# SchemaA-puissance.net
KiCad netlist of a schematic drawn in Altium Designer
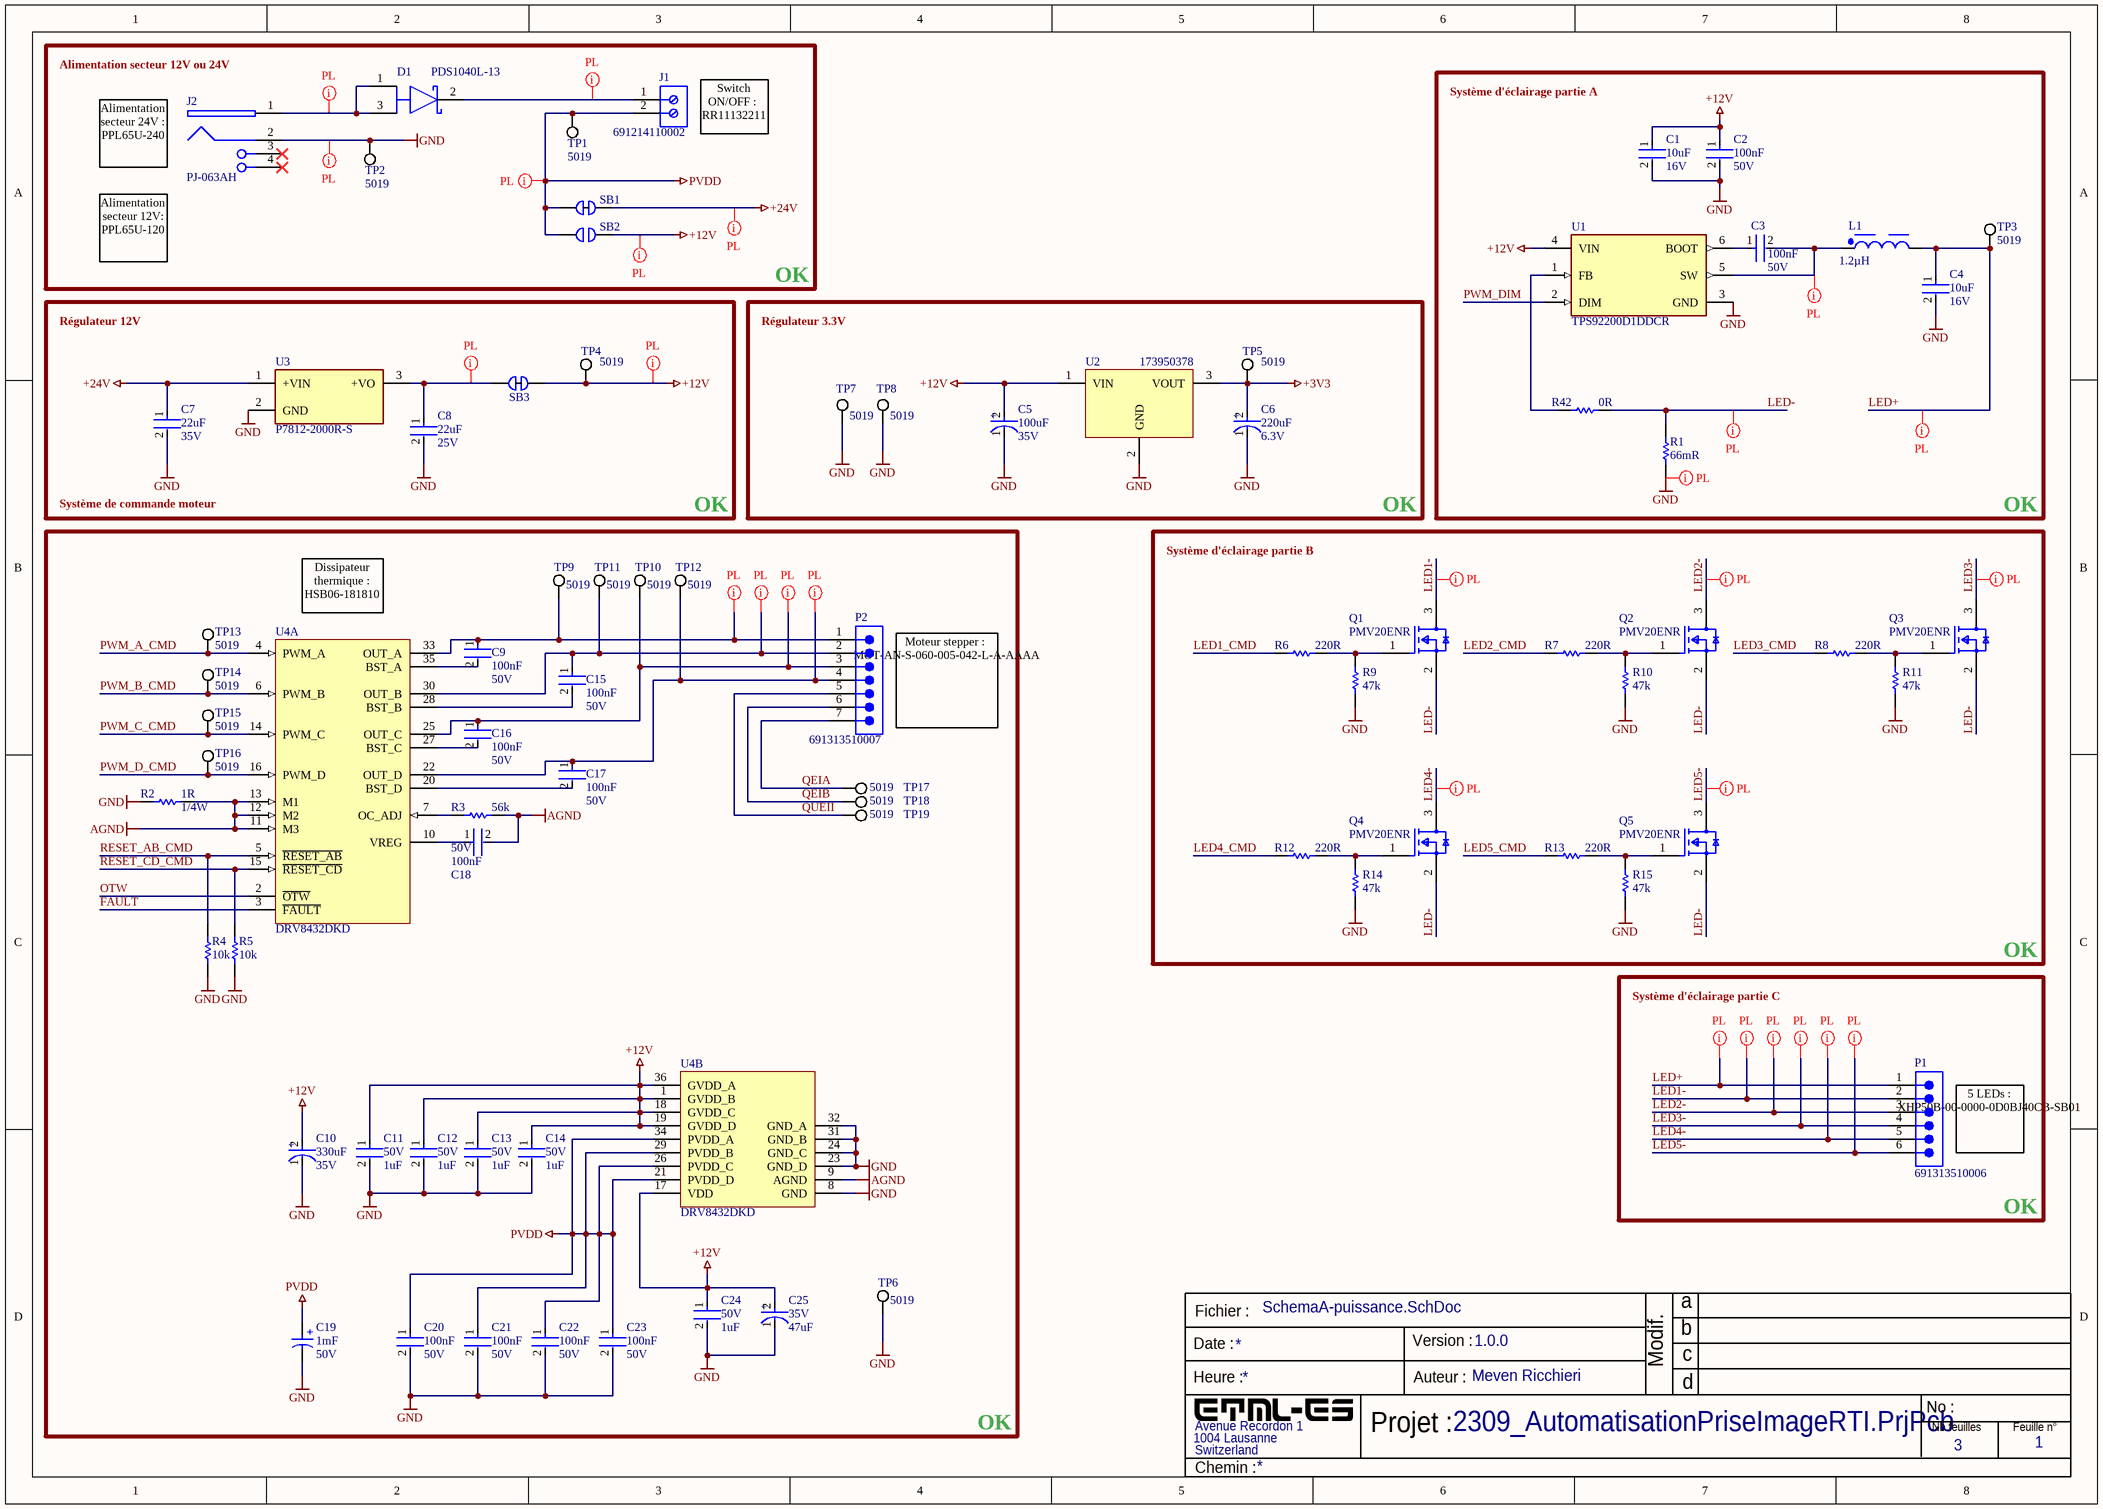
[diagram p0: SchemaA-puissance.SchDoc]

(export (version "E")
  (design (tool "Eeschema 10.0.6"))
  (components
    (comp (ref "C1")
      (value "CL21A106KOQNNNE")
      (footprint "FP-CL21-IPC_B")
      (description "CL21 Series 0805 10uF 16V ±10% Tolerance X5R Multilayer Ceramic Chip Capacitor")
      (fields
        (field (name "VOLTAGE") "16V")
        (field (name "CAPACITANCE") "10uF")
        (field (name "VOLTAGE RATING") "16V")
        (field (name "TOLERANCE") "10%")
      )
      (libsource (lib "Altium Content Vault") (part "b4654b650e69147ec39a6b967a45e02"))
    )
    (comp (ref "C2")
      (value "CL21B104KBCNNNC")
      (footprint "FP-CL21-IPC_C")
      (description "CL21 Series 0805 100nF 50V ±10% Tolerance X7R Multilayer Ceramic Chip Capacitor")
      (fields
        (field (name "TOLERANCE") "10%")
        (field (name "CAPACITANCE") "100nF")
        (field (name "VOLTAGE RATING") "50V")
        (field (name "VOLTAGE") "50V")
      )
      (libsource (lib "Altium Content Vault") (part "b4654b650e69147ec39a6b967a45e02"))
    )
    (comp (ref "C3")
      (value "CL21B104KBCNNNC")
      (footprint "FP-CL21-IPC_C")
      (description "CL21 Series 0805 100nF 50V ±10% Tolerance X7R Multilayer Ceramic Chip Capacitor")
      (fields
        (field (name "TOLERANCE") "10%")
        (field (name "CAPACITANCE") "100nF")
        (field (name "VOLTAGE RATING") "50V")
        (field (name "VOLTAGE") "50V")
      )
      (libsource (lib "Altium Content Vault") (part "b4654b650e69147ec39a6b967a45e02"))
    )
    (comp (ref "C4")
      (value "CL21A106KOQNNNE")
      (footprint "FP-CL21-IPC_B")
      (description "CL21 Series 0805 10uF 16V ±10% Tolerance X5R Multilayer Ceramic Chip Capacitor")
      (fields
        (field (name "VOLTAGE") "16V")
        (field (name "CAPACITANCE") "10uF")
        (field (name "VOLTAGE RATING") "16V")
        (field (name "TOLERANCE") "10%")
      )
      (libsource (lib "Altium Content Vault") (part "b4654b650e69147ec39a6b967a45e02"))
    )
    (comp (ref "C5")
      (value "EEE-1VA101XP")
      (footprint "FP-SD8-MFG")
      (description "CAP ALUM 100UF 20% 35V SMD")
      (fields
        (field (name "CAPACITANCE") "100uF")
        (field (name "TOLERANCE") "20%")
        (field (name "VOLTAGE") "35V")
      )
      (libsource (lib "Altium Content Vault") (part "a00bbbee19879c290e62620ae7e47b1"))
    )
    (comp (ref "C6")
      (value "EEE-FK0J221P")
      (footprint "FP-FKD-MFG")
      (description "CAP ALUM 220UF 20% 6.3V SMD")
      (fields
        (field (name "VOLTAGE RATING") "6.3V")
        (field (name "VOLTAGE") "6.3V")
        (field (name "CAPACITANCE") "220uF")
        (field (name "TOLERANCE") "20%")
      )
      (libsource (lib "Altium Content Vault") (part "a00bbbee19879c290e62620ae7e47b1"))
    )
    (comp (ref "C7")
      (value "GMK325BJ226MM-P")
      (footprint "FP-1210-L_3_2_0_3-W_2_5_0-MFG")
      (description "None")
      (fields
        (field (name "CAPACITANCE") "22uF")
        (field (name "VOLTAGE RATING") "35V")
        (field (name "TOLERANCE") "20%")
      )
      (libsource (lib "Altium Content Vault") (part "02cd4be3c70576c341d710602a673aa"))
    )
    (comp (ref "C8")
      (value "22uF")
      (footprint "FP-CL21-IPC_C")
      (description "CL21 Series 0805 22uF 25V ±20% Tolerance X5R Multilayer Ceramic Chip Capacitor")
      (fields (field (name "VOLTAGE") "25V") (field (name "Comment") "CL21A226MAYNNNE"))
      (libsource (lib "Altium Content Vault") (part "b4654b650e69147ec39a6b967a45e02"))
    )
    (comp (ref "C9")
      (value "CL21B104KBCNNNC")
      (footprint "FP-CL21-IPC_C")
      (description "CL21 Series 0805 100nF 50V ±10% Tolerance X7R Multilayer Ceramic Chip Capacitor")
      (fields
        (field (name "TOLERANCE") "10%")
        (field (name "CAPACITANCE") "100nF")
        (field (name "VOLTAGE RATING") "50V")
        (field (name "VOLTAGE") "50V")
      )
      (libsource (lib "Altium Content Vault") (part "b4654b650e69147ec39a6b967a45e02"))
    )
    (comp (ref "C10")
      (value "EEE-1VA331P")
      (footprint "FP-SG-MFG")
      (description "CAP ALUM 330UF 20% 35V SMD")
      (fields
        (field (name "VOLTAGE") "35V")
        (field (name "TOLERANCE") "20%")
        (field (name "CAPACITANCE") "330uF")
      )
      (libsource (lib "Altium Content Vault") (part "a00bbbee19879c290e62620ae7e47b1"))
    )
    (comp (ref "C11")
      (value "CL21B105KBFNNNG")
      (footprint "FP-CL21-IPC_C")
      (description "CL21 Series 0805 1uF 50V ±10% Tolerance X7R Multilayer Ceramic Chip Capacitor")
      (fields
        (field (name "CAPACITANCE") "1uF")
        (field (name "VOLTAGE") "50V")
        (field (name "TOLERANCE") "10%")
      )
      (libsource (lib "Altium Content Vault") (part "b4654b650e69147ec39a6b967a45e02"))
    )
    (comp (ref "C12")
      (value "CL21B105KBFNNNG")
      (footprint "FP-CL21-IPC_C")
      (description "CL21 Series 0805 1uF 50V ±10% Tolerance X7R Multilayer Ceramic Chip Capacitor")
      (fields
        (field (name "CAPACITANCE") "1uF")
        (field (name "VOLTAGE") "50V")
        (field (name "TOLERANCE") "10%")
      )
      (libsource (lib "Altium Content Vault") (part "b4654b650e69147ec39a6b967a45e02"))
    )
    (comp (ref "C13")
      (value "CL21B105KBFNNNG")
      (footprint "FP-CL21-IPC_C")
      (description "CL21 Series 0805 1uF 50V ±10% Tolerance X7R Multilayer Ceramic Chip Capacitor")
      (fields
        (field (name "CAPACITANCE") "1uF")
        (field (name "VOLTAGE") "50V")
        (field (name "TOLERANCE") "10%")
      )
      (libsource (lib "Altium Content Vault") (part "b4654b650e69147ec39a6b967a45e02"))
    )
    (comp (ref "C14")
      (value "CL21B105KBFNNNG")
      (footprint "FP-CL21-IPC_C")
      (description "CL21 Series 0805 1uF 50V ±10% Tolerance X7R Multilayer Ceramic Chip Capacitor")
      (fields
        (field (name "CAPACITANCE") "1uF")
        (field (name "VOLTAGE") "50V")
        (field (name "TOLERANCE") "10%")
      )
      (libsource (lib "Altium Content Vault") (part "b4654b650e69147ec39a6b967a45e02"))
    )
    (comp (ref "C15")
      (value "CL21B104KBCNNNC")
      (footprint "FP-CL21-IPC_C")
      (description "CL21 Series 0805 100nF 50V ±10% Tolerance X7R Multilayer Ceramic Chip Capacitor")
      (fields
        (field (name "TOLERANCE") "10%")
        (field (name "CAPACITANCE") "100nF")
        (field (name "VOLTAGE RATING") "50V")
        (field (name "VOLTAGE") "50V")
      )
      (libsource (lib "Altium Content Vault") (part "b4654b650e69147ec39a6b967a45e02"))
    )
    (comp (ref "C16")
      (value "CL21B104KBCNNNC")
      (footprint "FP-CL21-IPC_C")
      (description "CL21 Series 0805 100nF 50V ±10% Tolerance X7R Multilayer Ceramic Chip Capacitor")
      (fields
        (field (name "TOLERANCE") "10%")
        (field (name "CAPACITANCE") "100nF")
        (field (name "VOLTAGE RATING") "50V")
        (field (name "VOLTAGE") "50V")
      )
      (libsource (lib "Altium Content Vault") (part "b4654b650e69147ec39a6b967a45e02"))
    )
    (comp (ref "C17")
      (value "CL21B104KBCNNNC")
      (footprint "FP-CL21-IPC_C")
      (description "CL21 Series 0805 100nF 50V ±10% Tolerance X7R Multilayer Ceramic Chip Capacitor")
      (fields
        (field (name "TOLERANCE") "10%")
        (field (name "CAPACITANCE") "100nF")
        (field (name "VOLTAGE RATING") "50V")
        (field (name "VOLTAGE") "50V")
      )
      (libsource (lib "Altium Content Vault") (part "b4654b650e69147ec39a6b967a45e02"))
    )
    (comp (ref "C18")
      (value "CL21B104KBCNNNC")
      (footprint "FP-CL21-IPC_C")
      (description "CL21 Series 0805 100nF 50V ±10% Tolerance X7R Multilayer Ceramic Chip Capacitor")
      (fields
        (field (name "TOLERANCE") "10%")
        (field (name "CAPACITANCE") "100nF")
        (field (name "VOLTAGE RATING") "50V")
        (field (name "VOLTAGE") "50V")
      )
      (libsource (lib "Altium Content Vault") (part "b4654b650e69147ec39a6b967a45e02"))
    )
    (comp (ref "C19")
      (value "865080663020")
      (footprint "WCAP-ASLI_D16H17")
      (description "865080663020 WCAP-ASLI Aluminum Electrolytic Capacitors")
      (fields
        (field (name "CAPACITANCE") "1mF")
        (field (name "VOLTAGE RATING") "50V")
        (field (name "TOLERANCE") "20%")
      )
      (libsource (lib "Altium Content Vault") (part "Capacitor_Polarized"))
    )
    (comp (ref "C20")
      (value "CL21B104KBCNNNC")
      (footprint "FP-CL21-IPC_C")
      (description "CL21 Series 0805 100nF 50V ±10% Tolerance X7R Multilayer Ceramic Chip Capacitor")
      (fields
        (field (name "TOLERANCE") "10%")
        (field (name "CAPACITANCE") "100nF")
        (field (name "VOLTAGE RATING") "50V")
        (field (name "VOLTAGE") "50V")
      )
      (libsource (lib "Altium Content Vault") (part "b4654b650e69147ec39a6b967a45e02"))
    )
    (comp (ref "C21")
      (value "CL21B104KBCNNNC")
      (footprint "FP-CL21-IPC_C")
      (description "CL21 Series 0805 100nF 50V ±10% Tolerance X7R Multilayer Ceramic Chip Capacitor")
      (fields
        (field (name "TOLERANCE") "10%")
        (field (name "CAPACITANCE") "100nF")
        (field (name "VOLTAGE RATING") "50V")
        (field (name "VOLTAGE") "50V")
      )
      (libsource (lib "Altium Content Vault") (part "b4654b650e69147ec39a6b967a45e02"))
    )
    (comp (ref "C22")
      (value "CL21B104KBCNNNC")
      (footprint "FP-CL21-IPC_C")
      (description "CL21 Series 0805 100nF 50V ±10% Tolerance X7R Multilayer Ceramic Chip Capacitor")
      (fields
        (field (name "TOLERANCE") "10%")
        (field (name "CAPACITANCE") "100nF")
        (field (name "VOLTAGE RATING") "50V")
        (field (name "VOLTAGE") "50V")
      )
      (libsource (lib "Altium Content Vault") (part "b4654b650e69147ec39a6b967a45e02"))
    )
    (comp (ref "C23")
      (value "CL21B104KBCNNNC")
      (footprint "FP-CL21-IPC_C")
      (description "CL21 Series 0805 100nF 50V ±10% Tolerance X7R Multilayer Ceramic Chip Capacitor")
      (fields
        (field (name "TOLERANCE") "10%")
        (field (name "CAPACITANCE") "100nF")
        (field (name "VOLTAGE RATING") "50V")
        (field (name "VOLTAGE") "50V")
      )
      (libsource (lib "Altium Content Vault") (part "b4654b650e69147ec39a6b967a45e02"))
    )
    (comp (ref "C24")
      (value "CL21B105KBFNNNG")
      (footprint "FP-CL21-IPC_C")
      (description "CL21 Series 0805 1uF 50V ±10% Tolerance X7R Multilayer Ceramic Chip Capacitor")
      (fields
        (field (name "CAPACITANCE") "1uF")
        (field (name "VOLTAGE") "50V")
        (field (name "TOLERANCE") "10%")
      )
      (libsource (lib "Altium Content Vault") (part "b4654b650e69147ec39a6b967a45e02"))
    )
    (comp (ref "C25")
      (value "EEEFP1V470AP")
      (footprint "FP-FPD-MFG")
      (description "CAP ALUM 47UF 20% 35V SMD")
      (fields
        (field (name "VOLTAGE RATING (DC)") "35V")
        (field (name "TOLERANCE") "20%")
        (field (name "CAPACITANCE") "47uF")
        (field (name "VOLTAGE") "35V")
      )
      (libsource (lib "Altium Content Vault") (part "cf48714ba7e38822c1575c7ec0b6d1f"))
    )
    (comp (ref "D1")
      (value "PDS1040L-13")
      (footprint "FP-PowerDI5-MFG")
      (description "DIODE SCHOTTKY 40V 10A POWERDI5")
      (fields
        (field (name "OCTOPART") "https://octopart.com/pds1040l-13-diodes+inc.-332540")
        (field (name "MANUFACTURER") "Diodes Inc.")
      )
      (libsource (lib "Altium Content Vault") (part "742f7ab95c42997246ebbe41a6c66ae"))
    )
    (comp (ref "J1")
      (value "691214110002")
      (footprint "691214110002")
      (fields (field (name "VOLTAGE") "300V"))
      (libsource (lib "Altium Content Vault") (part "TBL - 1R - 02P - Screw"))
    )
    (comp (ref "J2")
      (value "PJ-063AH")
      (footprint "CUI-PJ-063AH_V")
      (fields (field (name "MANUFACTURER") "CUIInc."))
      (libsource (lib "Altium Content Vault") (part "JACK-2CD2_A"))
    )
    (comp (ref "L1")
      (value "7440430012")
      (footprint "WE-TPC_4828")
      (fields (field (name "TOLERANCE") "30%") (field (name "INDUCTANCE") "1.2µH"))
      (libsource (lib "Altium Content Vault") (part "Inductor - 2"))
    )
    (comp (ref "P1")
      (value "691313510006")
      (footprint "691313510006")
      (fields (field (name "VOLTAGE") "300V"))
      (libsource (lib "Altium Content Vault") (part "TBL - 1R - 06P - Male"))
    )
    (comp (ref "P2")
      (value "691313510007")
      (footprint "691313510007")
      (libsource (lib "Altium Content Vault") (part "TBL - 1R - 07P - Male"))
    )
    (comp (ref "Q1")
      (value "PMV20ENR")
      (footprint "FP-SOT23-MFG")
      (description "MOSFET N-CH 30V SOT23")
      (libsource (lib "Altium Content Vault") (part "0a9ea7c96deaaede766a5b531c28de0"))
    )
    (comp (ref "Q2")
      (value "PMV20ENR")
      (footprint "FP-SOT23-MFG")
      (description "MOSFET N-CH 30V SOT23")
      (libsource (lib "Altium Content Vault") (part "0a9ea7c96deaaede766a5b531c28de0"))
    )
    (comp (ref "Q3")
      (value "PMV20ENR")
      (footprint "FP-SOT23-MFG")
      (description "MOSFET N-CH 30V SOT23")
      (libsource (lib "Altium Content Vault") (part "0a9ea7c96deaaede766a5b531c28de0"))
    )
    (comp (ref "Q4")
      (value "PMV20ENR")
      (footprint "FP-SOT23-MFG")
      (description "MOSFET N-CH 30V SOT23")
      (libsource (lib "Altium Content Vault") (part "0a9ea7c96deaaede766a5b531c28de0"))
    )
    (comp (ref "Q5")
      (value "PMV20ENR")
      (footprint "FP-SOT23-MFG")
      (description "MOSFET N-CH 30V SOT23")
      (libsource (lib "Altium Content Vault") (part "0a9ea7c96deaaede766a5b531c28de0"))
    )
    (comp (ref "R1")
      (value "66mR")
      (footprint "6-0805_M")
      (description "Resistor")
      (fields (field (name "Comment") "ERJ-L06UF66MV") (field (name "PUBLISHER") "Altium Limited"))
      (libsource (lib "Miscellaneous Devices") (part "Res1"))
    )
    (comp (ref "R2")
      (value "1R")
      (footprint "RESC2013X60X30NL20T20")
      (fields
        (field (name "MANUFACTURER") "KOA Speer")
        (field (name "PART NUMBER") "RK73B2ATTD1R0J")
        (field (name "POWER") "1/4W")
      )
      (libsource (lib "Altium Content Vault") (part "RES"))
    )
    (comp (ref "R3")
      (value "56k")
      (footprint "RESC2013X70X40NL20T20")
      (fields (field (name "PART NUMBER") "ERJ6ENF5602V") (field (name "MANUFACTURER") "Panasonic"))
      (libsource (lib "Altium Content Vault") (part "RES"))
    )
    (comp (ref "R4")
      (value "RC0805JR-0710KL")
      (footprint "RESC2013X60X35ML10T20")
      (description "Chip Resistor, 10 KOhm, +/- 5%, 0.125 W, -55 to 155 degC, 0805 (2012 Metric), RoHS, Tape and Reel")
      (fields (field (name "MANUFACTURER") "Yageo") (field (name "RESISTANCE") "10k"))
      (libsource (lib "Altium Content Vault") (part "RES-2"))
    )
    (comp (ref "R5")
      (value "RC0805JR-0710KL")
      (footprint "RESC2013X60X35ML10T20")
      (description "Chip Resistor, 10 KOhm, +/- 5%, 0.125 W, -55 to 155 degC, 0805 (2012 Metric), RoHS, Tape and Reel")
      (fields (field (name "MANUFACTURER") "Yageo") (field (name "RESISTANCE") "10k"))
      (libsource (lib "Altium Content Vault") (part "RES-2"))
    )
    (comp (ref "R6")
      (value "220R")
      (footprint "RESC2013X70X40NL20T20")
      (fields (field (name "PART NUMBER") "ERJ6ENF2200V") (field (name "MANUFACTURER") "Panasonic"))
      (libsource (lib "Altium Content Vault") (part "RES"))
    )
    (comp (ref "R7")
      (value "220R")
      (footprint "RESC2013X70X40NL20T20")
      (fields (field (name "PART NUMBER") "ERJ6ENF2200V") (field (name "MANUFACTURER") "Panasonic"))
      (libsource (lib "Altium Content Vault") (part "RES"))
    )
    (comp (ref "R8")
      (value "220R")
      (footprint "RESC2013X70X40NL20T20")
      (fields (field (name "PART NUMBER") "ERJ6ENF2200V") (field (name "MANUFACTURER") "Panasonic"))
      (libsource (lib "Altium Content Vault") (part "RES"))
    )
    (comp (ref "R9")
      (value "47k")
      (footprint "RESC2013X60X35NL10T20")
      (description "Chip Resistor, 47 KOhm, +/- 1%, 0.125 W, -55 to 155 degC, 0805 (2012 Metric), RoHS, Tape and Reel")
      (fields (field (name "MANUFACTURER") "Yageo") (field (name "Comment") "RC0805FR-0747KL"))
      (libsource (lib "Altium Content Vault") (part "RES-2"))
    )
    (comp (ref "R10")
      (value "47k")
      (footprint "RESC2013X60X35NL10T20")
      (description "Chip Resistor, 47 KOhm, +/- 1%, 0.125 W, -55 to 155 degC, 0805 (2012 Metric), RoHS, Tape and Reel")
      (fields (field (name "MANUFACTURER") "Yageo") (field (name "Comment") "RC0805FR-0747KL"))
      (libsource (lib "Altium Content Vault") (part "RES-2"))
    )
    (comp (ref "R11")
      (value "47k")
      (footprint "RESC2013X60X35NL10T20")
      (description "Chip Resistor, 47 KOhm, +/- 1%, 0.125 W, -55 to 155 degC, 0805 (2012 Metric), RoHS, Tape and Reel")
      (fields (field (name "MANUFACTURER") "Yageo") (field (name "Comment") "RC0805FR-0747KL"))
      (libsource (lib "Altium Content Vault") (part "RES-2"))
    )
    (comp (ref "R12")
      (value "220R")
      (footprint "RESC2013X70X40NL20T20")
      (fields (field (name "PART NUMBER") "ERJ6ENF2200V") (field (name "MANUFACTURER") "Panasonic"))
      (libsource (lib "Altium Content Vault") (part "RES"))
    )
    (comp (ref "R13")
      (value "220R")
      (footprint "RESC2013X70X40NL20T20")
      (fields (field (name "PART NUMBER") "ERJ6ENF2200V") (field (name "MANUFACTURER") "Panasonic"))
      (libsource (lib "Altium Content Vault") (part "RES"))
    )
    (comp (ref "R14")
      (value "47k")
      (footprint "RESC2013X60X35NL10T20")
      (description "Chip Resistor, 47 KOhm, +/- 1%, 0.125 W, -55 to 155 degC, 0805 (2012 Metric), RoHS, Tape and Reel")
      (fields (field (name "MANUFACTURER") "Yageo") (field (name "Comment") "RC0805FR-0747KL"))
      (libsource (lib "Altium Content Vault") (part "RES-2"))
    )
    (comp (ref "R15")
      (value "47k")
      (footprint "RESC2013X60X35NL10T20")
      (description "Chip Resistor, 47 KOhm, +/- 1%, 0.125 W, -55 to 155 degC, 0805 (2012 Metric), RoHS, Tape and Reel")
      (fields (field (name "MANUFACTURER") "Yageo") (field (name "Comment") "RC0805FR-0747KL"))
      (libsource (lib "Altium Content Vault") (part "RES-2"))
    )
    (comp (ref "R42")
      (value "RC0805JR-070RL")
      (footprint "RESC2013X60X35ML10T20")
      (fields
        (field (name "RESISTANCE") "0R")
        (field (name "TOLERANCE") "5%")
        (field (name "MANUFACTURER") "Yageo")
      )
      (libsource (lib "Altium Content Vault") (part "RES-2"))
    )
    (comp (ref "SB1")
      (value "Solder bridge 3mm close")
      (footprint "Solder bridge")
      (libsource (lib "SymbLib") (part "Solder bridge 3mm close"))
    )
    (comp (ref "SB2")
      (value "Solder bridge 3mm open")
      (footprint "Solder bridge")
      (libsource (lib "SymbLib") (part "Solder bridge 3mm open"))
    )
    (comp (ref "SB3")
      (value "Solder bridge 3mm close")
      (footprint "Solder bridge")
      (libsource (lib "SymbLib") (part "Solder bridge 3mm close"))
    )
    (comp (ref "TP1")
      (value "5019")
      (footprint "KSTN-5019_V")
      (description "Test Point, 1 Position SMD, RoHS, Tape and Reel")
      (libsource (lib "Altium Content Vault") (part "TESTPOINT_WHITE"))
    )
    (comp (ref "TP2")
      (value "5019")
      (footprint "KSTN-5019_V")
      (description "Test Point, 1 Position SMD, RoHS, Tape and Reel")
      (libsource (lib "Altium Content Vault") (part "TESTPOINT_WHITE"))
    )
    (comp (ref "TP3")
      (value "5019")
      (footprint "KSTN-5019_V")
      (description "Test Point, 1 Position SMD, RoHS, Tape and Reel")
      (libsource (lib "Altium Content Vault") (part "TESTPOINT_WHITE"))
    )
    (comp (ref "TP4")
      (value "5019")
      (footprint "KSTN-5019_V")
      (description "Test Point, 1 Position SMD, RoHS, Tape and Reel")
      (libsource (lib "Altium Content Vault") (part "TESTPOINT_WHITE"))
    )
    (comp (ref "TP5")
      (value "5019")
      (footprint "KSTN-5019_V")
      (description "Test Point, 1 Position SMD, RoHS, Tape and Reel")
      (libsource (lib "Altium Content Vault") (part "TESTPOINT_WHITE"))
    )
    (comp (ref "TP6")
      (value "5019")
      (footprint "KSTN-5019_V")
      (description "Test Point, 1 Position SMD, RoHS, Tape and Reel")
      (libsource (lib "Altium Content Vault") (part "TESTPOINT_WHITE"))
    )
    (comp (ref "TP7")
      (value "5019")
      (footprint "KSTN-5019_V")
      (description "Test Point, 1 Position SMD, RoHS, Tape and Reel")
      (libsource (lib "Altium Content Vault") (part "TESTPOINT_WHITE"))
    )
    (comp (ref "TP8")
      (value "5019")
      (footprint "KSTN-5019_V")
      (description "Test Point, 1 Position SMD, RoHS, Tape and Reel")
      (libsource (lib "Altium Content Vault") (part "TESTPOINT_WHITE"))
    )
    (comp (ref "TP9")
      (value "5019")
      (footprint "KSTN-5019_V")
      (description "Test Point, 1 Position SMD, RoHS, Tape and Reel")
      (libsource (lib "Altium Content Vault") (part "TESTPOINT_WHITE"))
    )
    (comp (ref "TP10")
      (value "5019")
      (footprint "KSTN-5019_V")
      (description "Test Point, 1 Position SMD, RoHS, Tape and Reel")
      (libsource (lib "Altium Content Vault") (part "TESTPOINT_WHITE"))
    )
    (comp (ref "TP11")
      (value "5019")
      (footprint "KSTN-5019_V")
      (description "Test Point, 1 Position SMD, RoHS, Tape and Reel")
      (libsource (lib "Altium Content Vault") (part "TESTPOINT_WHITE"))
    )
    (comp (ref "TP12")
      (value "5019")
      (footprint "KSTN-5019_V")
      (description "Test Point, 1 Position SMD, RoHS, Tape and Reel")
      (libsource (lib "Altium Content Vault") (part "TESTPOINT_WHITE"))
    )
    (comp (ref "TP13")
      (value "5019")
      (footprint "KSTN-5019_V")
      (description "Test Point, 1 Position SMD, RoHS, Tape and Reel")
      (libsource (lib "Altium Content Vault") (part "TESTPOINT_WHITE"))
    )
    (comp (ref "TP14")
      (value "5019")
      (footprint "KSTN-5019_V")
      (description "Test Point, 1 Position SMD, RoHS, Tape and Reel")
      (libsource (lib "Altium Content Vault") (part "TESTPOINT_WHITE"))
    )
    (comp (ref "TP15")
      (value "5019")
      (footprint "KSTN-5019_V")
      (description "Test Point, 1 Position SMD, RoHS, Tape and Reel")
      (libsource (lib "Altium Content Vault") (part "TESTPOINT_WHITE"))
    )
    (comp (ref "TP16")
      (value "5019")
      (footprint "KSTN-5019_V")
      (description "Test Point, 1 Position SMD, RoHS, Tape and Reel")
      (libsource (lib "Altium Content Vault") (part "TESTPOINT_WHITE"))
    )
    (comp (ref "TP17")
      (value "5019")
      (footprint "KSTN-5019_V")
      (description "Test Point, 1 Position SMD, RoHS, Tape and Reel")
      (libsource (lib "Altium Content Vault") (part "TESTPOINT_WHITE"))
    )
    (comp (ref "TP18")
      (value "5019")
      (footprint "KSTN-5019_V")
      (description "Test Point, 1 Position SMD, RoHS, Tape and Reel")
      (libsource (lib "Altium Content Vault") (part "TESTPOINT_WHITE"))
    )
    (comp (ref "TP19")
      (value "5019")
      (footprint "KSTN-5019_V")
      (description "Test Point, 1 Position SMD, RoHS, Tape and Reel")
      (libsource (lib "Altium Content Vault") (part "TESTPOINT_WHITE"))
    )
    (comp (ref "U1")
      (value "TPS92200D1DDCR")
      (footprint "FP-DDC0006A-MFG")
      (libsource (lib "Altium Content Vault") (part "587de3e5279691f4f220b4264879a86"))
    )
    (comp (ref "U2")
      (value "173950378")
      (footprint "WPME-FDSM_SIP-3_L11.6W8.5H10.5")
      (description "173950378 Module DC-DC 1-OUT 3.3V 0.5A 3-Pin SIP Module Tube")
      (libsource (lib "Altium Content Vault") (part "SIP-3_WPME-FDSM"))
    )
    (comp (ref "U3")
      (value "P7812-2000R-S")
      (footprint "P7812-2000R-S")
      (libsource (lib "SymbLib") (part "P7812-2000R-S"))
    )
    (comp (ref "U4")
      (value "DRV8432DKD")
      (footprint "SOP65P1420X360-36N - duplicate")
      (libsource (lib "SymbLib") (part "DRV8432DKD"))
    )
  )
  (nets
    (net (code "1") (name "+3V3") (class "Default")
      (node (ref "C6") (pin "2") (pinfunction "A_2") (pintype "passive"))
      (node (ref "TP5") (pin "1") (pinfunction "1_1") (pintype "passive"))
      (node (ref "U2") (pin "3") (pinfunction "VOUT_3") (pintype "passive"))
    )
    (net (code "2") (name "+12V") (class "Default")
      (node (ref "C1") (pin "1") (pinfunction "1_1") (pintype "passive"))
      (node (ref "C10") (pin "2") (pinfunction "A_2") (pintype "passive"))
      (node (ref "C11") (pin "1") (pinfunction "1_1") (pintype "passive"))
      (node (ref "C12") (pin "1") (pinfunction "1_1") (pintype "passive"))
      (node (ref "C13") (pin "1") (pinfunction "1_1") (pintype "passive"))
      (node (ref "C14") (pin "1") (pinfunction "1_1") (pintype "passive"))
      (node (ref "C2") (pin "1") (pinfunction "1_1") (pintype "passive"))
      (node (ref "C24") (pin "1") (pinfunction "1_1") (pintype "passive"))
      (node (ref "C25") (pin "2") (pinfunction "A_2") (pintype "passive"))
      (node (ref "C5") (pin "2") (pinfunction "A_2") (pintype "passive"))
      (node (ref "SB2") (pin "2") (pinfunction "2_2") (pintype "passive"))
      (node (ref "SB3") (pin "1") (pinfunction "1_1") (pintype "passive"))
      (node (ref "TP4") (pin "1") (pinfunction "1_1") (pintype "passive"))
      (node (ref "U1") (pin "4") (pinfunction "VIN_4") (pintype "power_in"))
      (node (ref "U2") (pin "1") (pinfunction "VIN_1") (pintype "passive"))
      (node (ref "U4") (pin "1") (pinfunction "GVDD_B_1") (pintype "power_in"))
      (node (ref "U4") (pin "17") (pinfunction "VDD_17") (pintype "power_in"))
      (node (ref "U4") (pin "18") (pinfunction "GVDD_C_18") (pintype "power_in"))
      (node (ref "U4") (pin "19") (pinfunction "GVDD_D_19") (pintype "power_in"))
      (node (ref "U4") (pin "36") (pinfunction "GVDD_A_36") (pintype "power_in"))
    )
    (net (code "3") (name "+24V") (class "Default")
      (node (ref "C7") (pin "1") (pinfunction "1_1") (pintype "passive"))
      (node (ref "SB1") (pin "2") (pinfunction "2_2") (pintype "passive"))
      (node (ref "U3") (pin "1") (pinfunction "+VIN_1") (pintype "passive"))
    )
    (net (code "4") (name "/FAULT") (class "Default")
      (node (ref "U4") (pin "3") (pinfunction "~{FAULT}_3") (pintype "open_collector"))
    )
    (net (code "5") (name "/LED+") (class "Default")
      (node (ref "C4") (pin "1") (pinfunction "1_1") (pintype "passive"))
      (node (ref "L1") (pin "2") (pinfunction "2_2") (pintype "passive"))
      (node (ref "P1") (pin "1") (pinfunction "1_1") (pintype "passive"))
      (node (ref "TP3") (pin "1") (pinfunction "1_1") (pintype "passive"))
    )
    (net (code "6") (name "/LED-") (class "Default")
      (node (ref "Q1") (pin "2") (pinfunction "S_2") (pintype "passive"))
      (node (ref "Q2") (pin "2") (pinfunction "S_2") (pintype "passive"))
      (node (ref "Q3") (pin "2") (pinfunction "S_2") (pintype "passive"))
      (node (ref "Q4") (pin "2") (pinfunction "S_2") (pintype "passive"))
      (node (ref "Q5") (pin "2") (pinfunction "S_2") (pintype "passive"))
      (node (ref "R1") (pin "2") (pinfunction "2_2") (pintype "passive"))
      (node (ref "R42") (pin "2") (pinfunction "2_2") (pintype "passive"))
    )
    (net (code "7") (name "/LED1-") (class "Default")
      (node (ref "P1") (pin "2") (pinfunction "2_2") (pintype "passive"))
      (node (ref "Q1") (pin "3") (pinfunction "D_3") (pintype "passive"))
    )
    (net (code "8") (name "/LED1_CMD") (class "Default")
      (node (ref "R6") (pin "1") (pinfunction "1_1") (pintype "passive"))
    )
    (net (code "9") (name "/LED2-") (class "Default")
      (node (ref "P1") (pin "3") (pinfunction "3_3") (pintype "passive"))
      (node (ref "Q2") (pin "3") (pinfunction "D_3") (pintype "passive"))
    )
    (net (code "10") (name "/LED2_CMD") (class "Default")
      (node (ref "R7") (pin "1") (pinfunction "1_1") (pintype "passive"))
    )
    (net (code "11") (name "/LED3-") (class "Default")
      (node (ref "P1") (pin "4") (pinfunction "4_4") (pintype "passive"))
      (node (ref "Q3") (pin "3") (pinfunction "D_3") (pintype "passive"))
    )
    (net (code "12") (name "/LED3_CMD") (class "Default")
      (node (ref "R8") (pin "1") (pinfunction "1_1") (pintype "passive"))
    )
    (net (code "13") (name "/LED4-") (class "Default")
      (node (ref "P1") (pin "5") (pinfunction "5_5") (pintype "passive"))
      (node (ref "Q4") (pin "3") (pinfunction "D_3") (pintype "passive"))
    )
    (net (code "14") (name "/LED4_CMD") (class "Default")
      (node (ref "R12") (pin "1") (pinfunction "1_1") (pintype "passive"))
    )
    (net (code "15") (name "/LED5-") (class "Default")
      (node (ref "P1") (pin "6") (pinfunction "6_6") (pintype "passive"))
      (node (ref "Q5") (pin "3") (pinfunction "D_3") (pintype "passive"))
    )
    (net (code "16") (name "/LED5_CMD") (class "Default")
      (node (ref "R13") (pin "1") (pinfunction "1_1") (pintype "passive"))
    )
    (net (code "17") (name "/OTW") (class "Default")
      (node (ref "U4") (pin "2") (pinfunction "~{OTW}_2") (pintype "open_collector"))
    )
    (net (code "18") (name "/PWM_A_CMD") (class "Default")
      (node (ref "TP13") (pin "1") (pinfunction "1_1") (pintype "passive"))
      (node (ref "U4") (pin "4") (pinfunction "PWM_A_4") (pintype "input"))
    )
    (net (code "19") (name "/PWM_B_CMD") (class "Default")
      (node (ref "TP14") (pin "1") (pinfunction "1_1") (pintype "passive"))
      (node (ref "U4") (pin "6") (pinfunction "PWM_B_6") (pintype "input"))
    )
    (net (code "20") (name "/PWM_C_CMD") (class "Default")
      (node (ref "TP15") (pin "1") (pinfunction "1_1") (pintype "passive"))
      (node (ref "U4") (pin "14") (pinfunction "PWM_C_14") (pintype "input"))
    )
    (net (code "21") (name "/PWM_DIM") (class "Default")
      (node (ref "U1") (pin "2") (pinfunction "DIM_2") (pintype "input"))
    )
    (net (code "22") (name "/PWM_D_CMD") (class "Default")
      (node (ref "TP16") (pin "1") (pinfunction "1_1") (pintype "passive"))
      (node (ref "U4") (pin "16") (pinfunction "PWM_D_16") (pintype "input"))
    )
    (net (code "23") (name "/QEIA") (class "Default")
      (node (ref "P2") (pin "7") (pinfunction "7_7") (pintype "passive"))
      (node (ref "TP17") (pin "1") (pinfunction "1_1") (pintype "passive"))
    )
    (net (code "24") (name "/QEIB") (class "Default")
      (node (ref "P2") (pin "6") (pinfunction "6_6") (pintype "passive"))
      (node (ref "TP18") (pin "1") (pinfunction "1_1") (pintype "passive"))
    )
    (net (code "25") (name "/QUEII") (class "Default")
      (node (ref "P2") (pin "5") (pinfunction "5_5") (pintype "passive"))
      (node (ref "TP19") (pin "1") (pinfunction "1_1") (pintype "passive"))
    )
    (net (code "26") (name "/RESET_AB_CMD") (class "Default")
      (node (ref "R4") (pin "2") (pinfunction "2_2") (pintype "passive"))
      (node (ref "U4") (pin "5") (pinfunction "~{RESET_AB}_5") (pintype "input"))
    )
    (net (code "27") (name "/RESET_CD_CMD") (class "Default")
      (node (ref "R5") (pin "2") (pinfunction "2_2") (pintype "passive"))
      (node (ref "U4") (pin "15") (pinfunction "~{RESET_CD}_15") (pintype "input"))
    )
    (net (code "28") (name "AGND") (class "Default")
      (node (ref "C18") (pin "2") (pinfunction "2_2") (pintype "passive"))
      (node (ref "R2") (pin "2") (pinfunction "2_2") (pintype "passive"))
      (node (ref "R3") (pin "2") (pinfunction "2_2") (pintype "passive"))
      (node (ref "U4") (pin "11") (pinfunction "M3_11") (pintype "input"))
      (node (ref "U4") (pin "12") (pinfunction "M2_12") (pintype "input"))
      (node (ref "U4") (pin "13") (pinfunction "M1_13") (pintype "input"))
      (node (ref "U4") (pin "9") (pinfunction "AGND_9") (pintype "power_in"))
    )
    (net (code "29") (name "GND") (class "Default")
      (node (ref "C1") (pin "2") (pinfunction "2_2") (pintype "passive"))
      (node (ref "C10") (pin "1") (pinfunction "C_1") (pintype "passive"))
      (node (ref "C11") (pin "2") (pinfunction "2_2") (pintype "passive"))
      (node (ref "C12") (pin "2") (pinfunction "2_2") (pintype "passive"))
      (node (ref "C13") (pin "2") (pinfunction "2_2") (pintype "passive"))
      (node (ref "C14") (pin "2") (pinfunction "2_2") (pintype "passive"))
      (node (ref "C19") (pin "2") (pinfunction "N_2") (pintype "passive"))
      (node (ref "C2") (pin "2") (pinfunction "2_2") (pintype "passive"))
      (node (ref "C20") (pin "2") (pinfunction "2_2") (pintype "passive"))
      (node (ref "C21") (pin "2") (pinfunction "2_2") (pintype "passive"))
      (node (ref "C22") (pin "2") (pinfunction "2_2") (pintype "passive"))
      (node (ref "C23") (pin "2") (pinfunction "2_2") (pintype "passive"))
      (node (ref "C24") (pin "2") (pinfunction "2_2") (pintype "passive"))
      (node (ref "C25") (pin "1") (pinfunction "C_1") (pintype "passive"))
      (node (ref "C4") (pin "2") (pinfunction "2_2") (pintype "passive"))
      (node (ref "C5") (pin "1") (pinfunction "C_1") (pintype "passive"))
      (node (ref "C6") (pin "1") (pinfunction "C_1") (pintype "passive"))
      (node (ref "C7") (pin "2") (pinfunction "2_2") (pintype "passive"))
      (node (ref "C8") (pin "2") (pinfunction "2_2") (pintype "passive"))
      (node (ref "J2") (pin "2") (pinfunction "2_2") (pintype "passive"))
      (node (ref "R1") (pin "1") (pinfunction "1_1") (pintype "passive"))
      (node (ref "R10") (pin "1") (pinfunction "1_1") (pintype "passive"))
      (node (ref "R11") (pin "1") (pinfunction "1_1") (pintype "passive"))
      (node (ref "R14") (pin "1") (pinfunction "1_1") (pintype "passive"))
      (node (ref "R15") (pin "1") (pinfunction "1_1") (pintype "passive"))
      (node (ref "R2") (pin "1") (pinfunction "1_1") (pintype "passive"))
      (node (ref "R4") (pin "1") (pinfunction "1_1") (pintype "passive"))
      (node (ref "R5") (pin "1") (pinfunction "1_1") (pintype "passive"))
      (node (ref "R9") (pin "1") (pinfunction "1_1") (pintype "passive"))
      (node (ref "TP2") (pin "1") (pinfunction "1_1") (pintype "passive"))
      (node (ref "TP6") (pin "1") (pinfunction "1_1") (pintype "passive"))
      (node (ref "TP7") (pin "1") (pinfunction "1_1") (pintype "passive"))
      (node (ref "TP8") (pin "1") (pinfunction "1_1") (pintype "passive"))
      (node (ref "U1") (pin "3") (pinfunction "GND_3") (pintype "power_in"))
      (node (ref "U2") (pin "2") (pinfunction "GND_2") (pintype "passive"))
      (node (ref "U3") (pin "2") (pinfunction "GND_2") (pintype "power_in"))
      (node (ref "U4") (pin "23") (pinfunction "GND_D_23") (pintype "power_in"))
      (node (ref "U4") (pin "24") (pinfunction "GND_C_24") (pintype "power_in"))
      (node (ref "U4") (pin "31") (pinfunction "GND_B_31") (pintype "power_in"))
      (node (ref "U4") (pin "32") (pinfunction "GND_A_32") (pintype "power_in"))
      (node (ref "U4") (pin "8") (pinfunction "GND_8") (pintype "power_in"))
    )
    (net (code "30") (name "Net-(D1-A-Pad1)") (class "Default")
      (node (ref "D1") (pin "1") (pinfunction "A_1") (pintype "passive"))
      (node (ref "D1") (pin "3") (pinfunction "A_3") (pintype "passive"))
      (node (ref "J2") (pin "1") (pinfunction "1_1") (pintype "passive"))
    )
    (net (code "31") (name "Net-(D1-C)") (class "Default")
      (node (ref "D1") (pin "2") (pinfunction "C_2") (pintype "passive"))
      (node (ref "J1") (pin "1") (pinfunction "1_1") (pintype "passive"))
    )
    (net (code "32") (name "Net-(Q1-G)") (class "Default")
      (node (ref "Q1") (pin "1") (pinfunction "G_1") (pintype "passive"))
      (node (ref "R6") (pin "2") (pinfunction "2_2") (pintype "passive"))
      (node (ref "R9") (pin "2") (pinfunction "2_2") (pintype "passive"))
    )
    (net (code "33") (name "Net-(Q2-G)") (class "Default")
      (node (ref "Q2") (pin "1") (pinfunction "G_1") (pintype "passive"))
      (node (ref "R10") (pin "2") (pinfunction "2_2") (pintype "passive"))
      (node (ref "R7") (pin "2") (pinfunction "2_2") (pintype "passive"))
    )
    (net (code "34") (name "Net-(Q3-G)") (class "Default")
      (node (ref "Q3") (pin "1") (pinfunction "G_1") (pintype "passive"))
      (node (ref "R11") (pin "2") (pinfunction "2_2") (pintype "passive"))
      (node (ref "R8") (pin "2") (pinfunction "2_2") (pintype "passive"))
    )
    (net (code "35") (name "Net-(Q4-G)") (class "Default")
      (node (ref "Q4") (pin "1") (pinfunction "G_1") (pintype "passive"))
      (node (ref "R12") (pin "2") (pinfunction "2_2") (pintype "passive"))
      (node (ref "R14") (pin "2") (pinfunction "2_2") (pintype "passive"))
    )
    (net (code "36") (name "Net-(Q5-G)") (class "Default")
      (node (ref "Q5") (pin "1") (pinfunction "G_1") (pintype "passive"))
      (node (ref "R13") (pin "2") (pinfunction "2_2") (pintype "passive"))
      (node (ref "R15") (pin "2") (pinfunction "2_2") (pintype "passive"))
    )
    (net (code "37") (name "Net-(U1-BOOT)") (class "Default")
      (node (ref "C3") (pin "1") (pinfunction "1_1") (pintype "passive"))
      (node (ref "U1") (pin "6") (pinfunction "BOOT_6") (pintype "output"))
    )
    (net (code "38") (name "Net-(U1-FB)") (class "Default")
      (node (ref "R42") (pin "1") (pinfunction "1_1") (pintype "passive"))
      (node (ref "U1") (pin "1") (pinfunction "FB_1") (pintype "input"))
    )
    (net (code "39") (name "Net-(U1-SW)") (class "Default")
      (node (ref "C3") (pin "2") (pinfunction "2_2") (pintype "passive"))
      (node (ref "L1") (pin "1") (pinfunction "1_1") (pintype "passive"))
      (node (ref "U1") (pin "5") (pinfunction "SW_5") (pintype "output"))
    )
    (net (code "40") (name "Net-(U3-+VO)") (class "Default")
      (node (ref "C8") (pin "1") (pinfunction "1_1") (pintype "passive"))
      (node (ref "SB3") (pin "2") (pinfunction "2_2") (pintype "passive"))
      (node (ref "U3") (pin "3") (pinfunction "+VO_3") (pintype "passive"))
    )
    (net (code "41") (name "Net-(U4A-BST_A)") (class "Default")
      (node (ref "C9") (pin "2") (pinfunction "2_2") (pintype "passive"))
      (node (ref "U4") (pin "35") (pinfunction "BST_A_35") (pintype "passive"))
    )
    (net (code "42") (name "Net-(U4A-BST_B)") (class "Default")
      (node (ref "C15") (pin "2") (pinfunction "2_2") (pintype "passive"))
      (node (ref "U4") (pin "28") (pinfunction "BST_B_28") (pintype "passive"))
    )
    (net (code "43") (name "Net-(U4A-BST_C)") (class "Default")
      (node (ref "C16") (pin "2") (pinfunction "2_2") (pintype "passive"))
      (node (ref "U4") (pin "27") (pinfunction "BST_C_27") (pintype "passive"))
    )
    (net (code "44") (name "Net-(U4A-BST_D)") (class "Default")
      (node (ref "C17") (pin "2") (pinfunction "2_2") (pintype "passive"))
      (node (ref "U4") (pin "20") (pinfunction "BST_D_20") (pintype "passive"))
    )
    (net (code "45") (name "Net-(U4A-OC_ADJ)") (class "Default")
      (node (ref "R3") (pin "1") (pinfunction "1_1") (pintype "passive"))
      (node (ref "U4") (pin "7") (pinfunction "OC_ADJ_7") (pintype "input"))
    )
    (net (code "46") (name "Net-(U4A-OUT_A)") (class "Default")
      (node (ref "C9") (pin "1") (pinfunction "1_1") (pintype "passive"))
      (node (ref "P2") (pin "1") (pinfunction "1_1") (pintype "passive"))
      (node (ref "TP9") (pin "1") (pinfunction "1_1") (pintype "passive"))
      (node (ref "U4") (pin "33") (pinfunction "OUT_A_33") (pintype "tri_state"))
    )
    (net (code "47") (name "Net-(U4A-OUT_B)") (class "Default")
      (node (ref "C15") (pin "1") (pinfunction "1_1") (pintype "passive"))
      (node (ref "P2") (pin "2") (pinfunction "2_2") (pintype "passive"))
      (node (ref "TP11") (pin "1") (pinfunction "1_1") (pintype "passive"))
      (node (ref "U4") (pin "30") (pinfunction "OUT_B_30") (pintype "tri_state"))
    )
    (net (code "48") (name "Net-(U4A-OUT_C)") (class "Default")
      (node (ref "C16") (pin "1") (pinfunction "1_1") (pintype "passive"))
      (node (ref "P2") (pin "3") (pinfunction "3_3") (pintype "passive"))
      (node (ref "TP10") (pin "1") (pinfunction "1_1") (pintype "passive"))
      (node (ref "U4") (pin "25") (pinfunction "OUT_C_25") (pintype "tri_state"))
    )
    (net (code "49") (name "Net-(U4A-OUT_D)") (class "Default")
      (node (ref "C17") (pin "1") (pinfunction "1_1") (pintype "passive"))
      (node (ref "P2") (pin "4") (pinfunction "4_4") (pintype "passive"))
      (node (ref "TP12") (pin "1") (pinfunction "1_1") (pintype "passive"))
      (node (ref "U4") (pin "22") (pinfunction "OUT_D_22") (pintype "tri_state"))
    )
    (net (code "50") (name "Net-(U4A-VREG)") (class "Default")
      (node (ref "C18") (pin "1") (pinfunction "1_1") (pintype "passive"))
      (node (ref "U4") (pin "10") (pinfunction "VREG_10") (pintype "passive"))
    )
    (net (code "51") (name "PVDD") (class "Default")
      (node (ref "C19") (pin "1") (pinfunction "P_1") (pintype "passive"))
      (node (ref "C20") (pin "1") (pinfunction "1_1") (pintype "passive"))
      (node (ref "C21") (pin "1") (pinfunction "1_1") (pintype "passive"))
      (node (ref "C22") (pin "1") (pinfunction "1_1") (pintype "passive"))
      (node (ref "C23") (pin "1") (pinfunction "1_1") (pintype "passive"))
      (node (ref "J1") (pin "2") (pinfunction "2_2") (pintype "passive"))
      (node (ref "SB1") (pin "1") (pinfunction "1_1") (pintype "passive"))
      (node (ref "SB2") (pin "1") (pinfunction "1_1") (pintype "passive"))
      (node (ref "TP1") (pin "1") (pinfunction "1_1") (pintype "passive"))
      (node (ref "U4") (pin "21") (pinfunction "PVDD_D_21") (pintype "power_in"))
      (node (ref "U4") (pin "26") (pinfunction "PVDD_C_26") (pintype "power_in"))
      (node (ref "U4") (pin "29") (pinfunction "PVDD_B_29") (pintype "power_in"))
      (node (ref "U4") (pin "34") (pinfunction "PVDD_A_34") (pintype "power_in"))
    )
    (net (code "52") (name "unconnected-(J2-SHLD-Pad3)") (class "Default")
      (node (ref "J2") (pin "3") (pinfunction "SHLD_3") (pintype "passive+no_connect"))
    )
    (net (code "53") (name "unconnected-(J2-SHLD-Pad4)") (class "Default")
      (node (ref "J2") (pin "4") (pinfunction "SHLD_4") (pintype "passive+no_connect"))
    )
  )
)
